# APC1_Sensors.net
KiCad netlist of a schematic drawn in Altium Designer
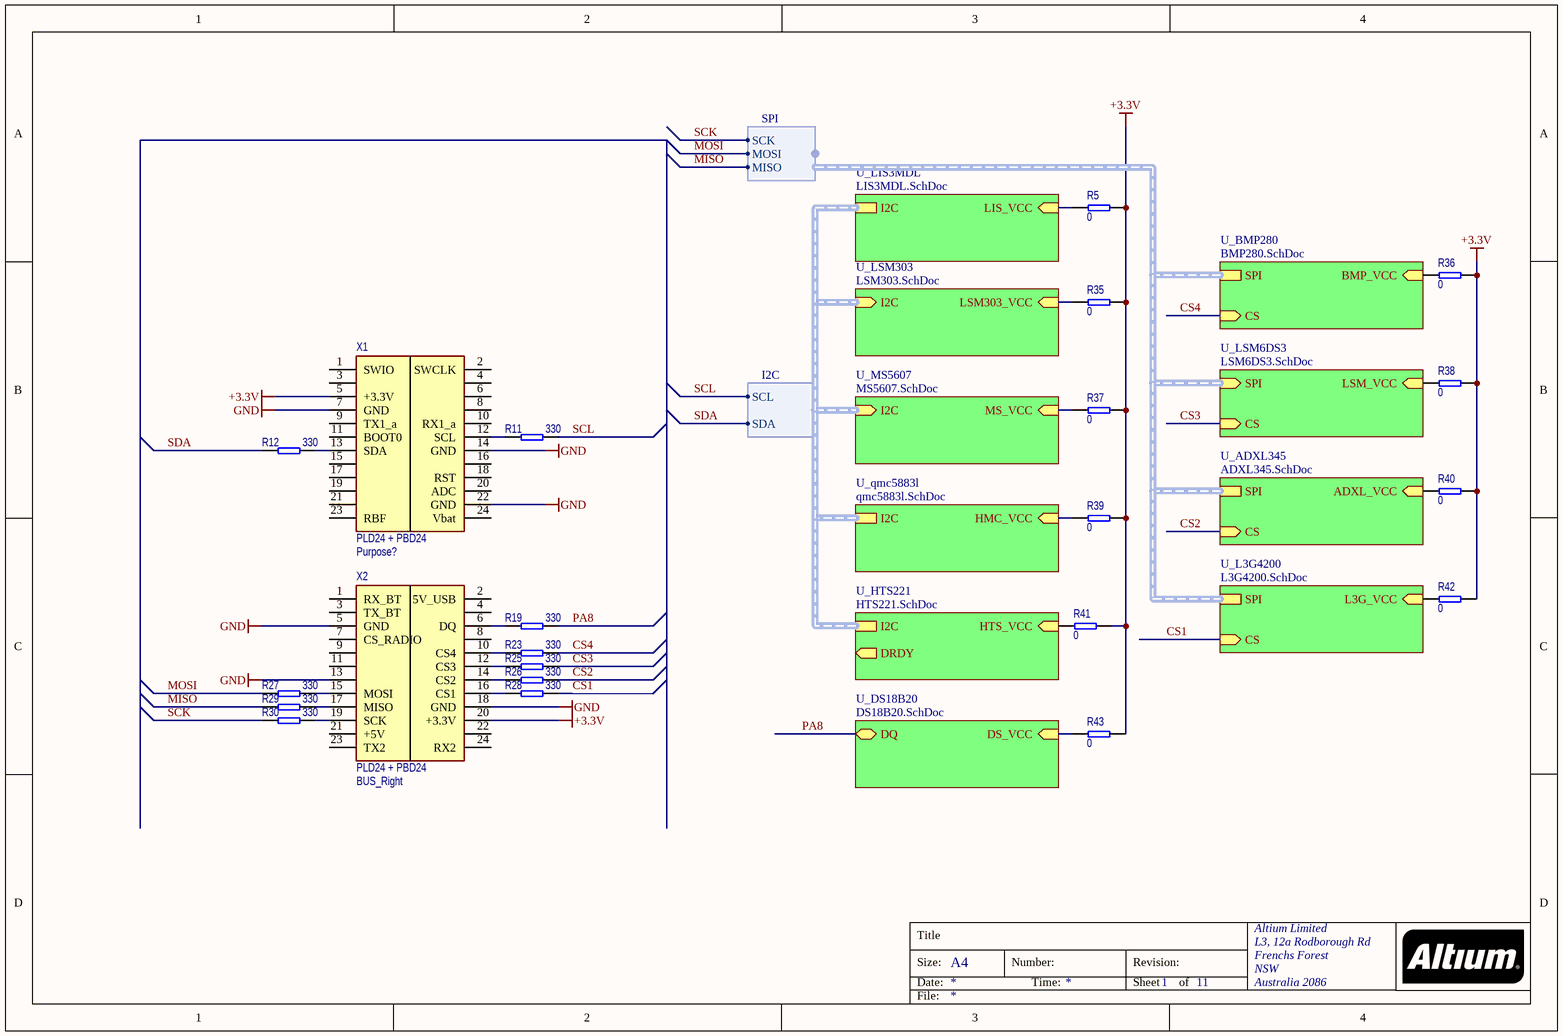
[diagram p0: APC1_Sensors.SchDoc]

(export (version "E")
  (design (tool "Eeschema 10.0.6"))
  (components
    (comp (ref "R5")
      (value "0")
      (footprint "RES 0603")
      (description "Resistor")
      (fields (field (name "Comment") "RES 0603 0"))
      (libsource (lib "!main") (part "!Resistor"))
    )
    (comp (ref "R11")
      (value "330")
      (footprint "RES 0402")
      (description "Resistor")
      (fields (field (name "Comment") "RES 0402 330"))
      (libsource (lib "!main") (part "!Resistor"))
    )
    (comp (ref "R12")
      (value "330")
      (footprint "RES 0402")
      (description "Resistor")
      (fields (field (name "Comment") "RES 0402 330"))
      (libsource (lib "!main") (part "!Resistor"))
    )
    (comp (ref "R19")
      (value "330")
      (footprint "RES 0402")
      (description "Resistor")
      (fields (field (name "Comment") "RES 0402 330"))
      (libsource (lib "!main") (part "!Resistor"))
    )
    (comp (ref "R23")
      (value "330")
      (footprint "RES 0402")
      (description "Resistor")
      (fields (field (name "Comment") "RES 0402 330"))
      (libsource (lib "!main") (part "!Resistor"))
    )
    (comp (ref "R25")
      (value "330")
      (footprint "RES 0402")
      (description "Resistor")
      (fields (field (name "Comment") "RES 0402 330"))
      (libsource (lib "!main") (part "!Resistor"))
    )
    (comp (ref "R26")
      (value "330")
      (footprint "RES 0402")
      (description "Resistor")
      (fields (field (name "Comment") "RES 0402 330"))
      (libsource (lib "!main") (part "!Resistor"))
    )
    (comp (ref "R27")
      (value "330")
      (footprint "RES 0402")
      (description "Resistor")
      (fields (field (name "Comment") "RES 0402 330"))
      (libsource (lib "!main") (part "!Resistor"))
    )
    (comp (ref "R28")
      (value "330")
      (footprint "RES 0402")
      (description "Resistor")
      (fields (field (name "Comment") "RES 0402 330"))
      (libsource (lib "!main") (part "!Resistor"))
    )
    (comp (ref "R29")
      (value "330")
      (footprint "RES 0402")
      (description "Resistor")
      (fields (field (name "Comment") "RES 0402 330"))
      (libsource (lib "!main") (part "!Resistor"))
    )
    (comp (ref "R30")
      (value "330")
      (footprint "RES 0402")
      (description "Resistor")
      (fields (field (name "Comment") "RES 0402 330"))
      (libsource (lib "!main") (part "!Resistor"))
    )
    (comp (ref "R35")
      (value "0")
      (footprint "RES 0603")
      (description "Resistor")
      (fields (field (name "Comment") "RES 0603 0"))
      (libsource (lib "!main") (part "!Resistor"))
    )
    (comp (ref "R36")
      (value "0")
      (footprint "RES 0603")
      (description "Resistor")
      (fields (field (name "Comment") "RES 0603 0"))
      (libsource (lib "!main") (part "!Resistor"))
    )
    (comp (ref "R37")
      (value "0")
      (footprint "RES 0603")
      (description "Resistor")
      (fields (field (name "Comment") "RES 0603 0"))
      (libsource (lib "!main") (part "!Resistor"))
    )
    (comp (ref "R38")
      (value "0")
      (footprint "RES 0603")
      (description "Resistor")
      (fields (field (name "Comment") "RES 0603 0"))
      (libsource (lib "!main") (part "!Resistor"))
    )
    (comp (ref "R39")
      (value "0")
      (footprint "RES 0603")
      (description "Resistor")
      (fields (field (name "Comment") "RES 0603 0"))
      (libsource (lib "!main") (part "!Resistor"))
    )
    (comp (ref "R40")
      (value "0")
      (footprint "RES 0603")
      (description "Resistor")
      (fields (field (name "Comment") "RES 0603 0"))
      (libsource (lib "!main") (part "!Resistor"))
    )
    (comp (ref "R41")
      (value "0")
      (footprint "RES 0603")
      (description "Resistor")
      (fields (field (name "Comment") "RES 0603 0"))
      (libsource (lib "!main") (part "!Resistor"))
    )
    (comp (ref "R42")
      (value "0")
      (footprint "RES 0603")
      (description "Resistor")
      (fields (field (name "Comment") "RES 0603 0"))
      (libsource (lib "!main") (part "!Resistor"))
    )
    (comp (ref "R43")
      (value "0")
      (footprint "RES 0603")
      (description "Resistor")
      (fields (field (name "Comment") "RES 0603 0"))
      (libsource (lib "!main") (part "!Resistor"))
    )
    (comp (ref "X1")
      (value "PLD24 + PBD24")
      (footprint "PICOSAT_CNN")
      (description "10x2 header")
      (fields (field (name "PURPOSE") "Purpose?"))
      (libsource (lib "connectors") (part "Header 2x12"))
    )
    (comp (ref "X2")
      (value "PLD24 + PBD24")
      (footprint "PICOSAT_CNN")
      (description "10x2 header")
      (fields (field (name "PURPOSE") "BUS_Right"))
      (libsource (lib "connectors") (part "Header 2x12"))
    )
  )
  (nets
    (net (code "3") (name "+3.3V") (class "Default")
      (node (ref "R35") (pin "2") (pinfunction "12_2") (pintype "passive"))
      (node (ref "R36") (pin "2") (pinfunction "12_2") (pintype "passive"))
      (node (ref "R37") (pin "2") (pinfunction "12_2") (pintype "passive"))
      (node (ref "R38") (pin "2") (pinfunction "12_2") (pintype "passive"))
      (node (ref "R39") (pin "2") (pinfunction "12_2") (pintype "passive"))
      (node (ref "R40") (pin "2") (pinfunction "12_2") (pintype "passive"))
      (node (ref "R41") (pin "2") (pinfunction "12_2") (pintype "passive"))
      (node (ref "R42") (pin "2") (pinfunction "12_2") (pintype "passive"))
      (node (ref "R43") (pin "2") (pinfunction "12_2") (pintype "passive"))
      (node (ref "R5") (pin "2") (pinfunction "12_2") (pintype "passive"))
      (node (ref "X1") (pin "5") (pinfunction "+3.3V_5") (pintype "passive"))
      (node (ref "X2") (pin "20") (pinfunction "ADC_20") (pintype "passive"))
    )
    (net (code "4") (name "/ADXL_VCC") (class "Default")
      (node (ref "R40") (pin "1") (pinfunction "11_1") (pintype "passive"))
    )
    (net (code "5") (name "/BMP_VCC") (class "Default")
      (node (ref "R36") (pin "1") (pinfunction "11_1") (pintype "passive"))
    )
    (net (code "6") (name "/CS1") (class "Default")
      (node (ref "R28") (pin "2") (pinfunction "12_2") (pintype "passive"))
    )
    (net (code "7") (name "/CS2") (class "Default")
      (node (ref "R26") (pin "2") (pinfunction "12_2") (pintype "passive"))
    )
    (net (code "8") (name "/CS3") (class "Default")
      (node (ref "R25") (pin "2") (pinfunction "12_2") (pintype "passive"))
    )
    (net (code "9") (name "/CS4") (class "Default")
      (node (ref "R23") (pin "2") (pinfunction "12_2") (pintype "passive"))
    )
    (net (code "11") (name "/DS_VCC") (class "Default")
      (node (ref "R43") (pin "1") (pinfunction "11_1") (pintype "passive"))
    )
    (net (code "12") (name "/HMC_VCC") (class "Default")
      (node (ref "R39") (pin "1") (pinfunction "11_1") (pintype "passive"))
    )
    (net (code "13") (name "/HTS_VCC") (class "Default")
      (node (ref "R41") (pin "1") (pinfunction "11_1") (pintype "passive"))
    )
    (net (code "14") (name "/L3G_VCC") (class "Default")
      (node (ref "R42") (pin "1") (pinfunction "11_1") (pintype "passive"))
    )
    (net (code "15") (name "/LIS_VCC") (class "Default")
      (node (ref "R5") (pin "1") (pinfunction "11_1") (pintype "passive"))
    )
    (net (code "16") (name "/LSM303_VCC") (class "Default")
      (node (ref "R35") (pin "1") (pinfunction "11_1") (pintype "passive"))
    )
    (net (code "17") (name "/LSM_VCC") (class "Default")
      (node (ref "R38") (pin "1") (pinfunction "11_1") (pintype "passive"))
    )
    (net (code "18") (name "/MISO") (class "Default")
      (node (ref "R29") (pin "1") (pinfunction "11_1") (pintype "passive"))
    )
    (net (code "19") (name "/MOSI") (class "Default")
      (node (ref "R27") (pin "1") (pinfunction "11_1") (pintype "passive"))
    )
    (net (code "20") (name "/MS_VCC") (class "Default")
      (node (ref "R37") (pin "1") (pinfunction "11_1") (pintype "passive"))
    )
    (net (code "21") (name "/PA8") (class "Default")
      (node (ref "R19") (pin "2") (pinfunction "12_2") (pintype "passive"))
    )
    (net (code "22") (name "/SCK") (class "Default")
      (node (ref "R30") (pin "1") (pinfunction "11_1") (pintype "passive"))
    )
    (net (code "23") (name "/SCL") (class "Default")
      (node (ref "R11") (pin "2") (pinfunction "12_2") (pintype "passive"))
    )
    (net (code "24") (name "/SDA") (class "Default")
      (node (ref "R12") (pin "1") (pinfunction "11_1") (pintype "passive"))
    )
    (net (code "27") (name "GND") (class "Default")
      (node (ref "X1") (pin "14") (pinfunction "GND_14") (pintype "passive"))
      (node (ref "X1") (pin "22") (pinfunction "GND_22") (pintype "passive"))
      (node (ref "X1") (pin "7") (pinfunction "GND_7") (pintype "passive"))
      (node (ref "X2") (pin "13") (pinfunction "SDA_13") (pintype "passive"))
      (node (ref "X2") (pin "18") (pinfunction "RST_18") (pintype "passive"))
      (node (ref "X2") (pin "5") (pinfunction "+3.3V_5") (pintype "passive"))
    )
    (net (code "28") (name "Net-(R11-11)") (class "Default")
      (node (ref "R11") (pin "1") (pinfunction "11_1") (pintype "passive"))
      (node (ref "X1") (pin "12") (pinfunction "SCL_12") (pintype "passive"))
    )
    (net (code "29") (name "Net-(R12-12)") (class "Default")
      (node (ref "R12") (pin "2") (pinfunction "12_2") (pintype "passive"))
      (node (ref "X1") (pin "13") (pinfunction "SDA_13") (pintype "passive"))
    )
    (net (code "30") (name "Net-(R19-11)") (class "Default")
      (node (ref "R19") (pin "1") (pinfunction "11_1") (pintype "passive"))
      (node (ref "X2") (pin "6") (pintype "passive"))
    )
    (net (code "31") (name "Net-(R23-11)") (class "Default")
      (node (ref "R23") (pin "1") (pinfunction "11_1") (pintype "passive"))
      (node (ref "X2") (pin "10") (pinfunction "RX1_a_10") (pintype "passive"))
    )
    (net (code "32") (name "Net-(R25-11)") (class "Default")
      (node (ref "R25") (pin "1") (pinfunction "11_1") (pintype "passive"))
      (node (ref "X2") (pin "12") (pinfunction "SCL_12") (pintype "passive"))
    )
    (net (code "33") (name "Net-(R26-11)") (class "Default")
      (node (ref "R26") (pin "1") (pinfunction "11_1") (pintype "passive"))
      (node (ref "X2") (pin "14") (pinfunction "GND_14") (pintype "passive"))
    )
    (net (code "34") (name "Net-(R27-12)") (class "Default")
      (node (ref "R27") (pin "2") (pinfunction "12_2") (pintype "passive"))
      (node (ref "X2") (pin "15") (pintype "passive"))
    )
    (net (code "35") (name "Net-(R28-11)") (class "Default")
      (node (ref "R28") (pin "1") (pinfunction "11_1") (pintype "passive"))
      (node (ref "X2") (pin "16") (pintype "passive"))
    )
    (net (code "36") (name "Net-(R29-12)") (class "Default")
      (node (ref "R29") (pin "2") (pinfunction "12_2") (pintype "passive"))
      (node (ref "X2") (pin "17") (pintype "passive"))
    )
    (net (code "37") (name "Net-(R30-12)") (class "Default")
      (node (ref "R30") (pin "2") (pinfunction "12_2") (pintype "passive"))
      (node (ref "X2") (pin "19") (pintype "passive"))
    )
    (net (code "38") (name "unconnected-(X1-ADC-Pad20)") (class "Default")
      (node (ref "X1") (pin "20") (pinfunction "ADC_20") (pintype "passive"))
    )
    (net (code "39") (name "unconnected-(X1-BOOT0-Pad11)") (class "Default")
      (node (ref "X1") (pin "11") (pinfunction "BOOT0_11") (pintype "passive"))
    )
    (net (code "40") (name "unconnected-(X1-Pad3)") (class "Default")
      (node (ref "X1") (pin "3") (pintype "passive"))
    )
    (net (code "41") (name "unconnected-(X1-Pad4)") (class "Default")
      (node (ref "X1") (pin "4") (pintype "passive"))
    )
    (net (code "42") (name "unconnected-(X1-Pad6)") (class "Default")
      (node (ref "X1") (pin "6") (pintype "passive"))
    )
    (net (code "43") (name "unconnected-(X1-Pad8)") (class "Default")
      (node (ref "X1") (pin "8") (pintype "passive"))
    )
    (net (code "44") (name "unconnected-(X1-Pad15)") (class "Default")
      (node (ref "X1") (pin "15") (pintype "passive"))
    )
    (net (code "45") (name "unconnected-(X1-Pad16)") (class "Default")
      (node (ref "X1") (pin "16") (pintype "passive"))
    )
    (net (code "46") (name "unconnected-(X1-Pad17)") (class "Default")
      (node (ref "X1") (pin "17") (pintype "passive"))
    )
    (net (code "47") (name "unconnected-(X1-Pad19)") (class "Default")
      (node (ref "X1") (pin "19") (pintype "passive"))
    )
    (net (code "48") (name "unconnected-(X1-Pad21)") (class "Default")
      (node (ref "X1") (pin "21") (pintype "passive"))
    )
    (net (code "49") (name "unconnected-(X1-RBF-Pad23)") (class "Default")
      (node (ref "X1") (pin "23") (pinfunction "RBF_23") (pintype "passive"))
    )
    (net (code "50") (name "unconnected-(X1-RST-Pad18)") (class "Default")
      (node (ref "X1") (pin "18") (pinfunction "RST_18") (pintype "passive"))
    )
    (net (code "51") (name "unconnected-(X1-RX1_a-Pad10)") (class "Default")
      (node (ref "X1") (pin "10") (pinfunction "RX1_a_10") (pintype "passive"))
    )
    (net (code "52") (name "unconnected-(X1-SWCLK-Pad2)") (class "Default")
      (node (ref "X1") (pin "2") (pinfunction "SWCLK_2") (pintype "passive"))
    )
    (net (code "53") (name "unconnected-(X1-SWIO-Pad1)") (class "Default")
      (node (ref "X1") (pin "1") (pinfunction "SWIO_1") (pintype "passive"))
    )
    (net (code "54") (name "unconnected-(X1-TX1_a-Pad9)") (class "Default")
      (node (ref "X1") (pin "9") (pinfunction "TX1_a_9") (pintype "passive"))
    )
    (net (code "55") (name "unconnected-(X1-Vbat-Pad24)") (class "Default")
      (node (ref "X1") (pin "24") (pinfunction "Vbat_24") (pintype "passive"))
    )
    (net (code "56") (name "unconnected-(X2-BOOT0-Pad11)") (class "Default")
      (node (ref "X2") (pin "11") (pinfunction "BOOT0_11") (pintype "passive"))
    )
    (net (code "57") (name "unconnected-(X2-GND-Pad7)") (class "Default")
      (node (ref "X2") (pin "7") (pinfunction "GND_7") (pintype "passive"))
    )
    (net (code "58") (name "unconnected-(X2-GND-Pad22)") (class "Default")
      (node (ref "X2") (pin "22") (pinfunction "GND_22") (pintype "passive"))
    )
    (net (code "59") (name "unconnected-(X2-Pad3)") (class "Default")
      (node (ref "X2") (pin "3") (pintype "passive"))
    )
    (net (code "60") (name "unconnected-(X2-Pad4)") (class "Default")
      (node (ref "X2") (pin "4") (pintype "passive"))
    )
    (net (code "61") (name "unconnected-(X2-Pad8)") (class "Default")
      (node (ref "X2") (pin "8") (pintype "passive"))
    )
    (net (code "62") (name "unconnected-(X2-Pad21)") (class "Default")
      (node (ref "X2") (pin "21") (pintype "passive"))
    )
    (net (code "63") (name "unconnected-(X2-RBF-Pad23)") (class "Default")
      (node (ref "X2") (pin "23") (pinfunction "RBF_23") (pintype "passive"))
    )
    (net (code "64") (name "unconnected-(X2-SWCLK-Pad2)") (class "Default")
      (node (ref "X2") (pin "2") (pinfunction "SWCLK_2") (pintype "passive"))
    )
    (net (code "65") (name "unconnected-(X2-SWIO-Pad1)") (class "Default")
      (node (ref "X2") (pin "1") (pinfunction "SWIO_1") (pintype "passive"))
    )
    (net (code "66") (name "unconnected-(X2-TX1_a-Pad9)") (class "Default")
      (node (ref "X2") (pin "9") (pinfunction "TX1_a_9") (pintype "passive"))
    )
    (net (code "67") (name "unconnected-(X2-Vbat-Pad24)") (class "Default")
      (node (ref "X2") (pin "24") (pinfunction "Vbat_24") (pintype "passive"))
    )
  )
)
